# DecoderCircuit_M1.net
KiCad netlist of a schematic drawn in Altium Designer
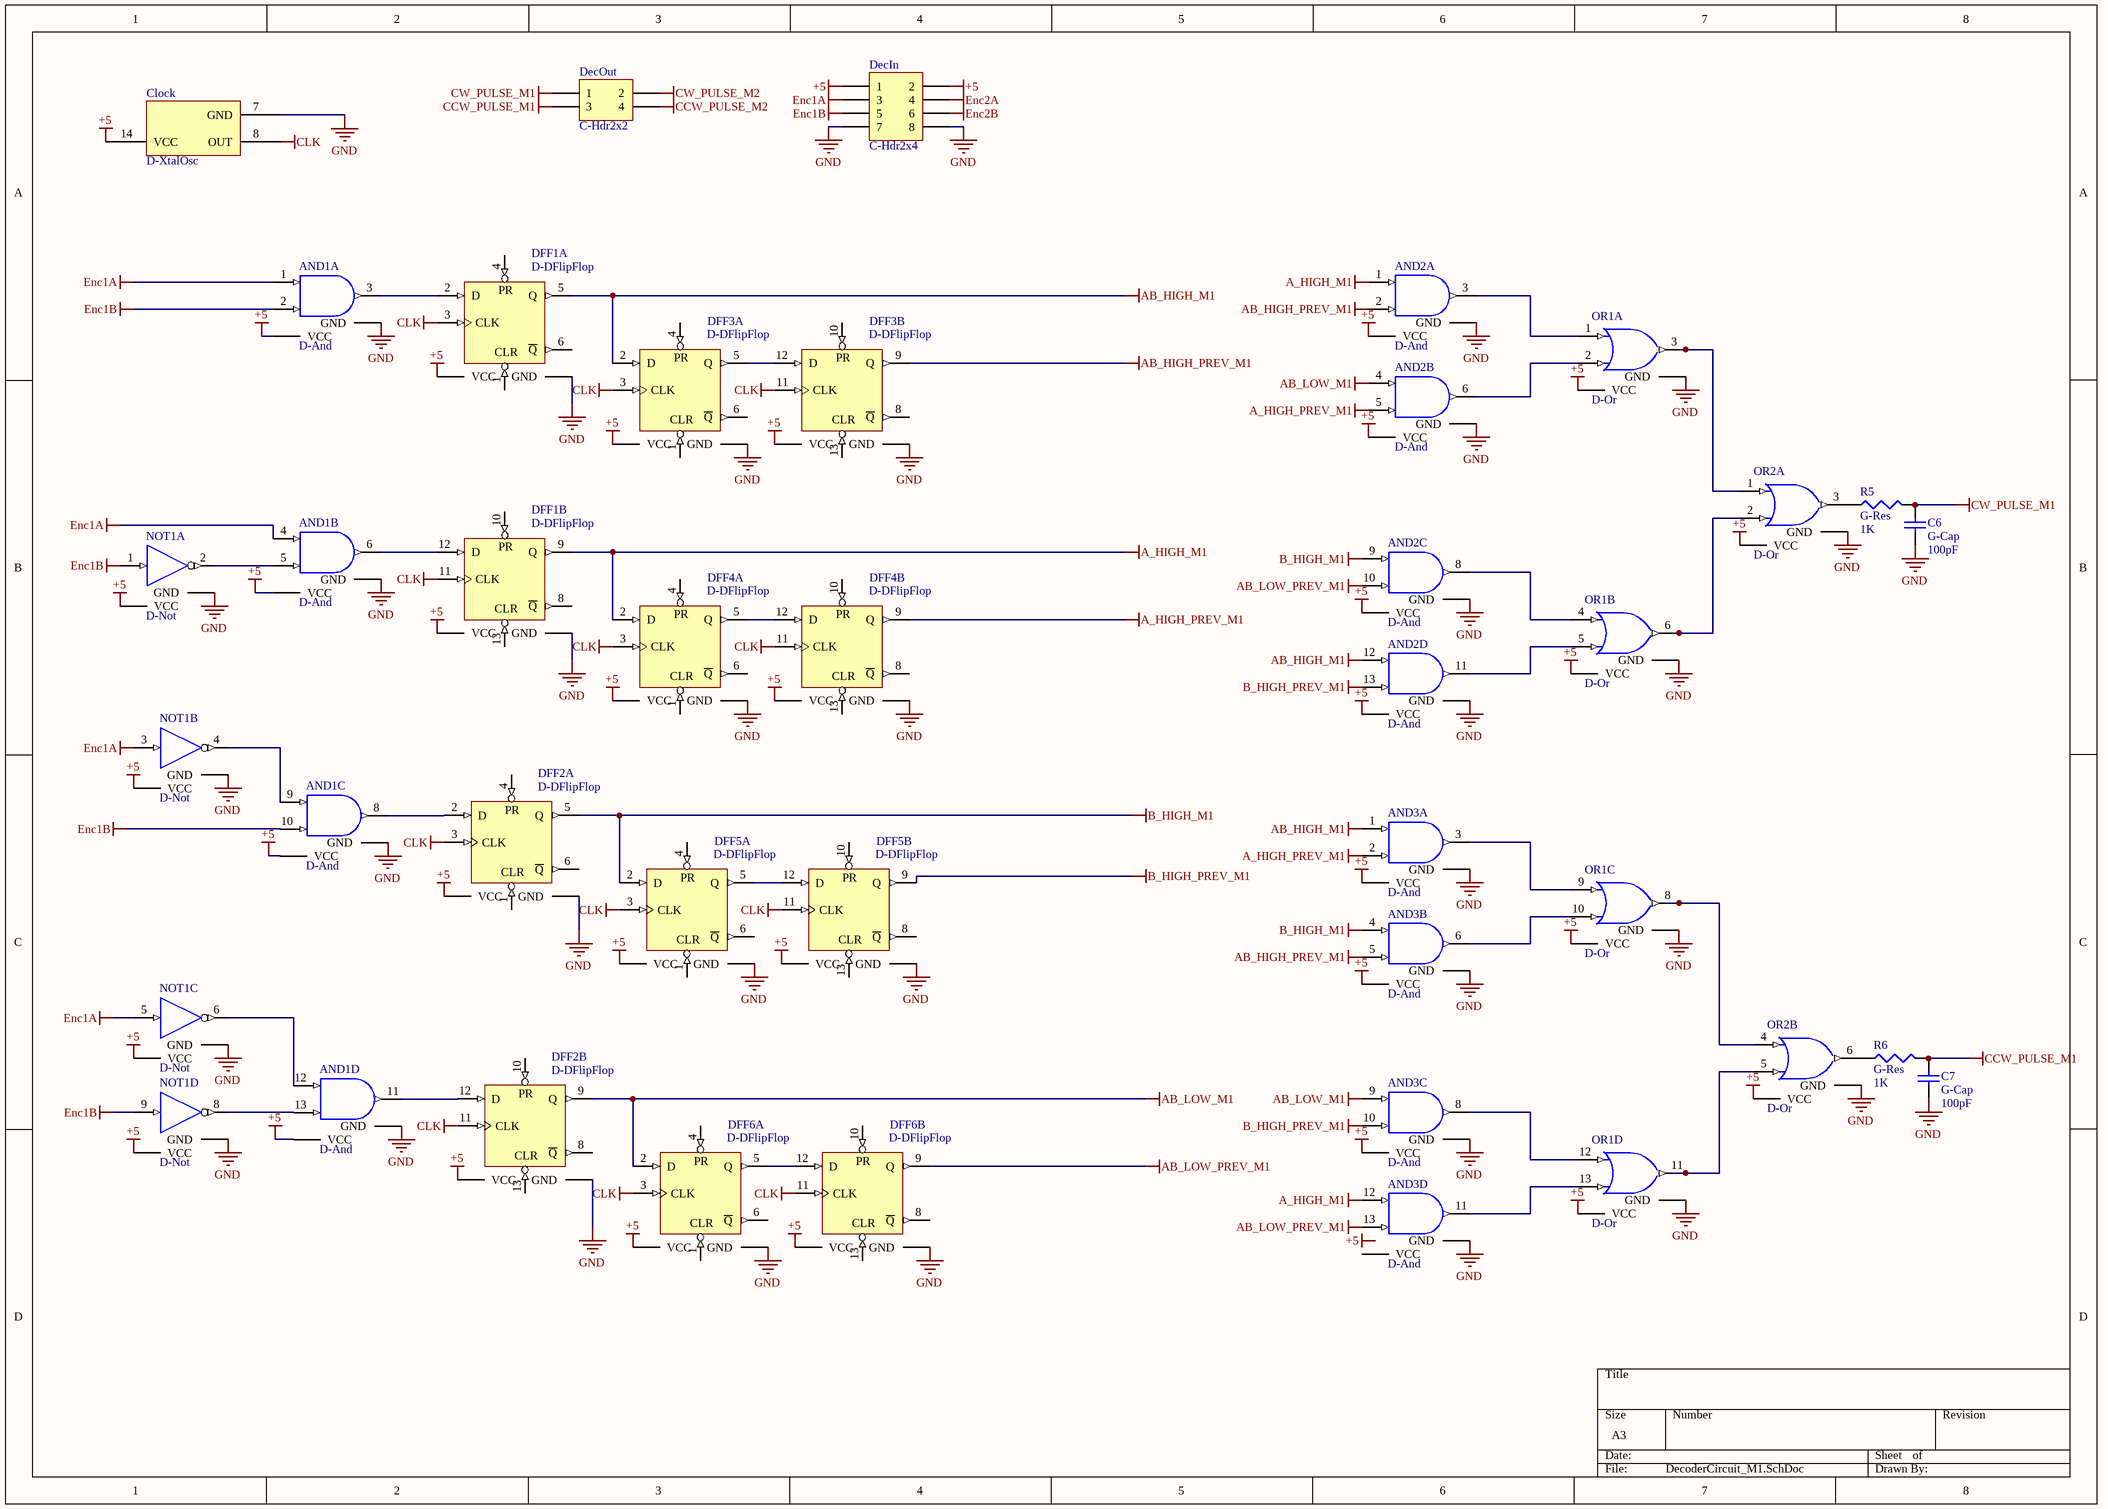
[diagram p0: DecoderCircuit_M1.SchDoc]

(export (version "E")
  (design (tool "Eeschema 10.0.6"))
  (components
    (comp (ref "AND1")
      (value "D-And")
      (footprint "DIP14_LGE1.0")
      (description "Quad 2-input AND gate")
      (fields (field (name "PUBLISHER") "Altium Limited"))
      (libsource (lib "PartsDatabaseV16.1") (part "D-And"))
    )
    (comp (ref "AND2")
      (value "D-And")
      (footprint "DIP14_LGE1.0")
      (description "Quad 2-input AND gate")
      (fields (field (name "PUBLISHER") "Altium Limited"))
      (libsource (lib "PartsDatabaseV16.1") (part "D-And"))
    )
    (comp (ref "AND3")
      (value "D-And")
      (footprint "DIP14_LGE1.0")
      (description "Quad 2-input AND gate")
      (fields (field (name "PUBLISHER") "Altium Limited"))
      (libsource (lib "PartsDatabaseV16.1") (part "D-And"))
    )
    (comp (ref "C6")
      (value "G-Cap")
      (footprint "Cap2.54mm_LGE1.0")
      (description "Capacitor (specify value)")
      (fields (field (name "ALTIUM_VALUE") "100pF") (field (name "PUBLISHER") "Altium Limited"))
      (libsource (lib "PartsDatabaseV16.1") (part "G-Cap"))
    )
    (comp (ref "C7")
      (value "G-Cap")
      (footprint "Cap2.54mm_LGE1.0")
      (description "Capacitor (specify value)")
      (fields (field (name "ALTIUM_VALUE") "100pF") (field (name "PUBLISHER") "Altium Limited"))
      (libsource (lib "PartsDatabaseV16.1") (part "G-Cap"))
    )
    (comp (ref "Clock")
      (value "D-XtalOsc")
      (footprint "4Lead Osc_LGE1.0")
      (description "Crystal Oscillator")
      (fields (field (name "PUBLISHER") "Altium Limited"))
      (libsource (lib "PartsDatabaseV16.1") (part "D-XtalOsc"))
    )
    (comp (ref "DecIn")
      (value "C-Hdr2x4")
      (footprint "HDR2X4_LGE1.0")
      (description "Header, 4-Pin, Dual row")
      (fields (field (name "PUBLISHER") "Altium Limited"))
      (libsource (lib "PartsDatabaseV16.1") (part "C-Hdr2x4"))
    )
    (comp (ref "DecOut")
      (value "C-Hdr2x2")
      (footprint "HDR2X2_LGE1.0")
      (description "Header, 2-Pin, Dual row")
      (fields (field (name "PUBLISHER") "Altium Limited"))
      (libsource (lib "PartsDatabaseV16.1") (part "C-Hdr2x2"))
    )
    (comp (ref "DFF1")
      (value "D-DFlipFlop")
      (footprint "DIP14_LGE1.0")
      (description "Dual D flip-flop")
      (fields (field (name "PUBLISHER") "Altium Limited"))
      (libsource (lib "PartsDatabaseV16.1") (part "D-DFlipFlop"))
    )
    (comp (ref "DFF2")
      (value "D-DFlipFlop")
      (footprint "DIP14_LGE1.0")
      (description "Dual D flip-flop")
      (fields (field (name "PUBLISHER") "Altium Limited"))
      (libsource (lib "PartsDatabaseV16.1") (part "D-DFlipFlop"))
    )
    (comp (ref "DFF3")
      (value "D-DFlipFlop")
      (footprint "DIP14_LGE1.0")
      (description "Dual D flip-flop")
      (fields (field (name "PUBLISHER") "Altium Limited"))
      (libsource (lib "PartsDatabaseV16.1") (part "D-DFlipFlop"))
    )
    (comp (ref "DFF4")
      (value "D-DFlipFlop")
      (footprint "DIP14_LGE1.0")
      (description "Dual D flip-flop")
      (fields (field (name "PUBLISHER") "Altium Limited"))
      (libsource (lib "PartsDatabaseV16.1") (part "D-DFlipFlop"))
    )
    (comp (ref "DFF5")
      (value "D-DFlipFlop")
      (footprint "DIP14_LGE1.0")
      (description "Dual D flip-flop")
      (fields (field (name "PUBLISHER") "Altium Limited"))
      (libsource (lib "PartsDatabaseV16.1") (part "D-DFlipFlop"))
    )
    (comp (ref "DFF6")
      (value "D-DFlipFlop")
      (footprint "DIP14_LGE1.0")
      (description "Dual D flip-flop")
      (fields (field (name "PUBLISHER") "Altium Limited"))
      (libsource (lib "PartsDatabaseV16.1") (part "D-DFlipFlop"))
    )
    (comp (ref "NOT1")
      (value "D-Not")
      (footprint "DIP14_LGE1.0")
      (description "Hex NOT gate (inverter)")
      (fields (field (name "PUBLISHER") "Altium Limited"))
      (libsource (lib "PartsDatabaseV16.1") (part "D-Not"))
    )
    (comp (ref "OR1")
      (value "D-Or")
      (footprint "DIP14_LGE1.0")
      (description "Quad 2-input OR gate")
      (fields (field (name "PUBLISHER") "Altium Limited"))
      (libsource (lib "PartsDatabaseV16.1") (part "D-Or"))
    )
    (comp (ref "OR2")
      (value "D-Or")
      (footprint "DIP14_LGE1.0")
      (description "Quad 2-input OR gate")
      (fields (field (name "PUBLISHER") "Altium Limited"))
      (libsource (lib "PartsDatabaseV16.1") (part "D-Or"))
    )
    (comp (ref "R5")
      (value "G-Res")
      (footprint "Res10mm_LGE1.0")
      (description "Resistor (specify value)")
      (fields (field (name "ALTIUM_VALUE") "1K") (field (name "PUBLISHER") "Altium Limited"))
      (libsource (lib "PartsDatabaseV16.1") (part "G-Res"))
    )
    (comp (ref "R6")
      (value "G-Res")
      (footprint "Res10mm_LGE1.0")
      (description "Resistor (specify value)")
      (fields (field (name "ALTIUM_VALUE") "1K") (field (name "PUBLISHER") "Altium Limited"))
      (libsource (lib "PartsDatabaseV16.1") (part "G-Res"))
    )
  )
  (nets
    (net (code "1") (name "+5") (class "Default")
      (node (ref "AND1") (pin "14") (pinfunction "VCC_14") (pintype "power_in"))
      (node (ref "AND2") (pin "14") (pinfunction "VCC_14") (pintype "power_in"))
      (node (ref "AND3") (pin "14") (pinfunction "VCC_14") (pintype "power_in"))
      (node (ref "Clock") (pin "14") (pinfunction "VCC_14") (pintype "passive"))
      (node (ref "DFF1") (pin "14") (pinfunction "VCC_14") (pintype "power_in"))
      (node (ref "DFF2") (pin "14") (pinfunction "VCC_14") (pintype "power_in"))
      (node (ref "DFF3") (pin "14") (pinfunction "VCC_14") (pintype "power_in"))
      (node (ref "DFF4") (pin "14") (pinfunction "VCC_14") (pintype "power_in"))
      (node (ref "DFF5") (pin "14") (pinfunction "VCC_14") (pintype "power_in"))
      (node (ref "DFF6") (pin "14") (pinfunction "VCC_14") (pintype "power_in"))
      (node (ref "DecIn") (pin "1") (pinfunction "1_1") (pintype "passive"))
      (node (ref "DecIn") (pin "2") (pinfunction "2_2") (pintype "passive"))
      (node (ref "NOT1") (pin "14") (pinfunction "VCC_14") (pintype "power_in"))
      (node (ref "OR1") (pin "14") (pinfunction "VCC_14") (pintype "power_in"))
      (node (ref "OR2") (pin "14") (pinfunction "VCC_14") (pintype "power_in"))
    )
    (net (code "2") (name "AB_HIGH_M1") (class "Default")
      (node (ref "AND2") (pin "12") (pinfunction "A_12") (pintype "input"))
      (node (ref "AND3") (pin "1") (pinfunction "A_1") (pintype "input"))
      (node (ref "DFF1") (pin "5") (pinfunction "Q_5") (pintype "output"))
      (node (ref "DFF3") (pin "2") (pinfunction "D_2") (pintype "input"))
    )
    (net (code "3") (name "AB_HIGH_PREV_M1") (class "Default")
      (node (ref "AND2") (pin "2") (pinfunction "B_2") (pintype "input"))
      (node (ref "AND3") (pin "5") (pinfunction "B_5") (pintype "input"))
      (node (ref "DFF3") (pin "9") (pinfunction "Q_9") (pintype "output"))
    )
    (net (code "4") (name "AB_LOW_M1") (class "Default")
      (node (ref "AND2") (pin "4") (pinfunction "A_4") (pintype "input"))
      (node (ref "AND3") (pin "9") (pinfunction "A_9") (pintype "input"))
      (node (ref "DFF2") (pin "9") (pinfunction "Q_9") (pintype "output"))
      (node (ref "DFF6") (pin "2") (pinfunction "D_2") (pintype "input"))
    )
    (net (code "5") (name "AB_LOW_PREV_M1") (class "Default")
      (node (ref "AND2") (pin "10") (pinfunction "B_10") (pintype "input"))
      (node (ref "AND3") (pin "13") (pinfunction "B_13") (pintype "input"))
      (node (ref "DFF6") (pin "9") (pinfunction "Q_9") (pintype "output"))
    )
    (net (code "6") (name "A_HIGH_M1") (class "Default")
      (node (ref "AND2") (pin "1") (pinfunction "A_1") (pintype "input"))
      (node (ref "AND3") (pin "12") (pinfunction "A_12") (pintype "input"))
      (node (ref "DFF1") (pin "9") (pinfunction "Q_9") (pintype "output"))
      (node (ref "DFF4") (pin "2") (pinfunction "D_2") (pintype "input"))
    )
    (net (code "7") (name "A_HIGH_PREV_M1") (class "Default")
      (node (ref "AND2") (pin "5") (pinfunction "B_5") (pintype "input"))
      (node (ref "AND3") (pin "2") (pinfunction "B_2") (pintype "input"))
      (node (ref "DFF4") (pin "9") (pinfunction "Q_9") (pintype "output"))
    )
    (net (code "8") (name "B_HIGH_M1") (class "Default")
      (node (ref "AND2") (pin "9") (pinfunction "A_9") (pintype "input"))
      (node (ref "AND3") (pin "4") (pinfunction "A_4") (pintype "input"))
      (node (ref "DFF2") (pin "5") (pinfunction "Q_5") (pintype "output"))
      (node (ref "DFF5") (pin "2") (pinfunction "D_2") (pintype "input"))
    )
    (net (code "9") (name "B_HIGH_PREV_M1") (class "Default")
      (node (ref "AND2") (pin "13") (pinfunction "B_13") (pintype "input"))
      (node (ref "AND3") (pin "10") (pinfunction "B_10") (pintype "input"))
      (node (ref "DFF5") (pin "9") (pinfunction "Q_9") (pintype "output"))
    )
    (net (code "10") (name "CCW_PULSE_M1") (class "Default")
      (node (ref "C7") (pin "1") (pinfunction "1_1") (pintype "passive"))
      (node (ref "DecOut") (pin "3") (pinfunction "3_3") (pintype "passive"))
      (node (ref "R6") (pin "2") (pinfunction "2_2") (pintype "passive"))
    )
    (net (code "11") (name "CCW_PULSE_M2") (class "Default")
      (node (ref "DecOut") (pin "4") (pinfunction "4_4") (pintype "passive"))
    )
    (net (code "12") (name "CLK") (class "Default")
      (node (ref "Clock") (pin "8") (pinfunction "OUT_8") (pintype "passive"))
      (node (ref "DFF1") (pin "11") (pinfunction "CLK_11") (pintype "input"))
      (node (ref "DFF1") (pin "3") (pinfunction "CLK_3") (pintype "input"))
      (node (ref "DFF2") (pin "11") (pinfunction "CLK_11") (pintype "input"))
      (node (ref "DFF2") (pin "3") (pinfunction "CLK_3") (pintype "input"))
      (node (ref "DFF3") (pin "11") (pinfunction "CLK_11") (pintype "input"))
      (node (ref "DFF3") (pin "3") (pinfunction "CLK_3") (pintype "input"))
      (node (ref "DFF4") (pin "11") (pinfunction "CLK_11") (pintype "input"))
      (node (ref "DFF4") (pin "3") (pinfunction "CLK_3") (pintype "input"))
      (node (ref "DFF5") (pin "11") (pinfunction "CLK_11") (pintype "input"))
      (node (ref "DFF5") (pin "3") (pinfunction "CLK_3") (pintype "input"))
      (node (ref "DFF6") (pin "11") (pinfunction "CLK_11") (pintype "input"))
      (node (ref "DFF6") (pin "3") (pinfunction "CLK_3") (pintype "input"))
    )
    (net (code "13") (name "CW_PULSE_M1") (class "Default")
      (node (ref "C6") (pin "1") (pinfunction "1_1") (pintype "passive"))
      (node (ref "DecOut") (pin "1") (pinfunction "1_1") (pintype "passive"))
      (node (ref "R5") (pin "2") (pinfunction "2_2") (pintype "passive"))
    )
    (net (code "14") (name "CW_PULSE_M2") (class "Default")
      (node (ref "DecOut") (pin "2") (pinfunction "2_2") (pintype "passive"))
    )
    (net (code "15") (name "Enc1A") (class "Default")
      (node (ref "AND1") (pin "1") (pinfunction "A_1") (pintype "input"))
      (node (ref "AND1") (pin "4") (pinfunction "A_4") (pintype "input"))
      (node (ref "DecIn") (pin "3") (pinfunction "3_3") (pintype "passive"))
      (node (ref "NOT1") (pin "3") (pinfunction "A_3") (pintype "input"))
      (node (ref "NOT1") (pin "5") (pinfunction "A_5") (pintype "input"))
    )
    (net (code "16") (name "Enc1B") (class "Default")
      (node (ref "AND1") (pin "10") (pinfunction "B_10") (pintype "input"))
      (node (ref "AND1") (pin "2") (pinfunction "B_2") (pintype "input"))
      (node (ref "DecIn") (pin "5") (pinfunction "5_5") (pintype "passive"))
      (node (ref "NOT1") (pin "1") (pinfunction "A_1") (pintype "input"))
      (node (ref "NOT1") (pin "9") (pinfunction "A_9") (pintype "input"))
    )
    (net (code "17") (name "Enc2A") (class "Default")
      (node (ref "DecIn") (pin "4") (pinfunction "4_4") (pintype "passive"))
    )
    (net (code "18") (name "Enc2B") (class "Default")
      (node (ref "DecIn") (pin "6") (pinfunction "6_6") (pintype "passive"))
    )
    (net (code "19") (name "GND") (class "Default")
      (node (ref "AND1") (pin "7") (pinfunction "GND_7") (pintype "power_in"))
      (node (ref "AND2") (pin "7") (pinfunction "GND_7") (pintype "power_in"))
      (node (ref "AND3") (pin "7") (pinfunction "GND_7") (pintype "power_in"))
      (node (ref "C6") (pin "2") (pinfunction "2_2") (pintype "passive"))
      (node (ref "C7") (pin "2") (pinfunction "2_2") (pintype "passive"))
      (node (ref "Clock") (pin "7") (pinfunction "GND_7") (pintype "passive"))
      (node (ref "DFF1") (pin "7") (pinfunction "GND_7") (pintype "power_in"))
      (node (ref "DFF2") (pin "7") (pinfunction "GND_7") (pintype "power_in"))
      (node (ref "DFF3") (pin "7") (pinfunction "GND_7") (pintype "power_in"))
      (node (ref "DFF4") (pin "7") (pinfunction "GND_7") (pintype "power_in"))
      (node (ref "DFF5") (pin "7") (pinfunction "GND_7") (pintype "power_in"))
      (node (ref "DFF6") (pin "7") (pinfunction "GND_7") (pintype "power_in"))
      (node (ref "DecIn") (pin "7") (pinfunction "7_7") (pintype "passive"))
      (node (ref "DecIn") (pin "8") (pinfunction "8_8") (pintype "passive"))
      (node (ref "NOT1") (pin "7") (pinfunction "GND_7") (pintype "power_in"))
      (node (ref "OR1") (pin "7") (pinfunction "GND_7") (pintype "power_in"))
      (node (ref "OR2") (pin "7") (pinfunction "GND_7") (pintype "power_in"))
    )
    (net (code "20") (name "Net-(AND1A-Y)") (class "Default")
      (node (ref "AND1") (pin "3") (pinfunction "Y_3") (pintype "output"))
      (node (ref "DFF1") (pin "2") (pinfunction "D_2") (pintype "input"))
    )
    (net (code "21") (name "Net-(AND1B-B)") (class "Default")
      (node (ref "AND1") (pin "5") (pinfunction "B_5") (pintype "input"))
      (node (ref "NOT1") (pin "2") (pinfunction "Y_2") (pintype "output"))
    )
    (net (code "22") (name "Net-(AND1B-Y)") (class "Default")
      (node (ref "AND1") (pin "6") (pinfunction "Y_6") (pintype "output"))
      (node (ref "DFF1") (pin "12") (pinfunction "D_12") (pintype "input"))
    )
    (net (code "23") (name "Net-(AND1C-A)") (class "Default")
      (node (ref "AND1") (pin "9") (pinfunction "A_9") (pintype "input"))
      (node (ref "NOT1") (pin "4") (pinfunction "Y_4") (pintype "output"))
    )
    (net (code "24") (name "Net-(AND1C-Y)") (class "Default")
      (node (ref "AND1") (pin "8") (pinfunction "Y_8") (pintype "output"))
      (node (ref "DFF2") (pin "2") (pinfunction "D_2") (pintype "input"))
    )
    (net (code "25") (name "Net-(AND1D-A)") (class "Default")
      (node (ref "AND1") (pin "12") (pinfunction "A_12") (pintype "input"))
      (node (ref "NOT1") (pin "6") (pinfunction "Y_6") (pintype "output"))
    )
    (net (code "26") (name "Net-(AND1D-B)") (class "Default")
      (node (ref "AND1") (pin "13") (pinfunction "B_13") (pintype "input"))
      (node (ref "NOT1") (pin "8") (pinfunction "Y_8") (pintype "output"))
    )
    (net (code "27") (name "Net-(AND1D-Y)") (class "Default")
      (node (ref "AND1") (pin "11") (pinfunction "Y_11") (pintype "output"))
      (node (ref "DFF2") (pin "12") (pinfunction "D_12") (pintype "input"))
    )
    (net (code "28") (name "Net-(AND2A-Y)") (class "Default")
      (node (ref "AND2") (pin "3") (pinfunction "Y_3") (pintype "output"))
      (node (ref "OR1") (pin "1") (pinfunction "A_1") (pintype "input"))
    )
    (net (code "29") (name "Net-(AND2B-Y)") (class "Default")
      (node (ref "AND2") (pin "6") (pinfunction "Y_6") (pintype "output"))
      (node (ref "OR1") (pin "2") (pinfunction "B_2") (pintype "input"))
    )
    (net (code "30") (name "Net-(AND2C-Y)") (class "Default")
      (node (ref "AND2") (pin "8") (pinfunction "Y_8") (pintype "output"))
      (node (ref "OR1") (pin "4") (pinfunction "A_4") (pintype "input"))
    )
    (net (code "31") (name "Net-(AND2D-Y)") (class "Default")
      (node (ref "AND2") (pin "11") (pinfunction "Y_11") (pintype "output"))
      (node (ref "OR1") (pin "5") (pinfunction "B_5") (pintype "input"))
    )
    (net (code "32") (name "Net-(AND3A-Y)") (class "Default")
      (node (ref "AND3") (pin "3") (pinfunction "Y_3") (pintype "output"))
      (node (ref "OR1") (pin "9") (pinfunction "A_9") (pintype "input"))
    )
    (net (code "33") (name "Net-(AND3B-Y)") (class "Default")
      (node (ref "AND3") (pin "6") (pinfunction "Y_6") (pintype "output"))
      (node (ref "OR1") (pin "10") (pinfunction "B_10") (pintype "input"))
    )
    (net (code "34") (name "Net-(AND3C-Y)") (class "Default")
      (node (ref "AND3") (pin "8") (pinfunction "Y_8") (pintype "output"))
      (node (ref "OR1") (pin "12") (pinfunction "A_12") (pintype "input"))
    )
    (net (code "35") (name "Net-(AND3D-Y)") (class "Default")
      (node (ref "AND3") (pin "11") (pinfunction "Y_11") (pintype "output"))
      (node (ref "OR1") (pin "13") (pinfunction "B_13") (pintype "input"))
    )
    (net (code "36") (name "Net-(DFF3A-Q)") (class "Default")
      (node (ref "DFF3") (pin "12") (pinfunction "D_12") (pintype "input"))
      (node (ref "DFF3") (pin "5") (pinfunction "Q_5") (pintype "output"))
    )
    (net (code "37") (name "Net-(DFF4A-Q)") (class "Default")
      (node (ref "DFF4") (pin "12") (pinfunction "D_12") (pintype "input"))
      (node (ref "DFF4") (pin "5") (pinfunction "Q_5") (pintype "output"))
    )
    (net (code "38") (name "Net-(DFF5A-Q)") (class "Default")
      (node (ref "DFF5") (pin "12") (pinfunction "D_12") (pintype "input"))
      (node (ref "DFF5") (pin "5") (pinfunction "Q_5") (pintype "output"))
    )
    (net (code "39") (name "Net-(DFF6A-Q)") (class "Default")
      (node (ref "DFF6") (pin "12") (pinfunction "D_12") (pintype "input"))
      (node (ref "DFF6") (pin "5") (pinfunction "Q_5") (pintype "output"))
    )
    (net (code "40") (name "Net-(OR1A-Y)") (class "Default")
      (node (ref "OR1") (pin "3") (pinfunction "Y_3") (pintype "output"))
      (node (ref "OR2") (pin "1") (pinfunction "A_1") (pintype "input"))
    )
    (net (code "41") (name "Net-(OR1B-Y)") (class "Default")
      (node (ref "OR1") (pin "6") (pinfunction "Y_6") (pintype "output"))
      (node (ref "OR2") (pin "2") (pinfunction "B_2") (pintype "input"))
    )
    (net (code "42") (name "Net-(OR1C-Y)") (class "Default")
      (node (ref "OR1") (pin "8") (pinfunction "Y_8") (pintype "output"))
      (node (ref "OR2") (pin "4") (pinfunction "A_4") (pintype "input"))
    )
    (net (code "43") (name "Net-(OR1D-Y)") (class "Default")
      (node (ref "OR1") (pin "11") (pinfunction "Y_11") (pintype "output"))
      (node (ref "OR2") (pin "5") (pinfunction "B_5") (pintype "input"))
    )
    (net (code "44") (name "Net-(OR2A-Y)") (class "Default")
      (node (ref "OR2") (pin "3") (pinfunction "Y_3") (pintype "output"))
      (node (ref "R5") (pin "1") (pinfunction "1_1") (pintype "passive"))
    )
    (net (code "45") (name "Net-(OR2B-Y)") (class "Default")
      (node (ref "OR2") (pin "6") (pinfunction "Y_6") (pintype "output"))
      (node (ref "R6") (pin "1") (pinfunction "1_1") (pintype "passive"))
    )
    (net (code "46") (name "unconnected-(AND3D-VCC-Pad14)") (class "Default")
      (node (ref "AND3") (pin "14") (pinfunction "VCC_14") (pintype "power_in"))
    )
    (net (code "47") (name "unconnected-(Clock-NC-Pad1)") (class "Default")
      (node (ref "Clock") (pin "1") (pinfunction "NC_1") (pintype "passive"))
    )
    (net (code "48") (name "unconnected-(DFF1A-CLR-Pad1)") (class "Default")
      (node (ref "DFF1") (pin "1") (pinfunction "CLR_1") (pintype "input"))
    )
    (net (code "49") (name "unconnected-(DFF1A-PR-Pad4)") (class "Default")
      (node (ref "DFF1") (pin "4") (pinfunction "PR_4") (pintype "input"))
    )
    (net (code "50") (name "unconnected-(DFF1A-~{Q}-Pad6)") (class "Default")
      (node (ref "DFF1") (pin "6") (pinfunction "~{Q}_6") (pintype "output"))
    )
    (net (code "51") (name "unconnected-(DFF1B-CLR-Pad13)") (class "Default")
      (node (ref "DFF1") (pin "13") (pinfunction "CLR_13") (pintype "input"))
    )
    (net (code "52") (name "unconnected-(DFF1B-PR-Pad10)") (class "Default")
      (node (ref "DFF1") (pin "10") (pinfunction "PR_10") (pintype "input"))
    )
    (net (code "53") (name "unconnected-(DFF1B-~{Q}-Pad8)") (class "Default")
      (node (ref "DFF1") (pin "8") (pinfunction "~{Q}_8") (pintype "output"))
    )
    (net (code "54") (name "unconnected-(DFF2A-CLR-Pad1)") (class "Default")
      (node (ref "DFF2") (pin "1") (pinfunction "CLR_1") (pintype "input"))
    )
    (net (code "55") (name "unconnected-(DFF2A-PR-Pad4)") (class "Default")
      (node (ref "DFF2") (pin "4") (pinfunction "PR_4") (pintype "input"))
    )
    (net (code "56") (name "unconnected-(DFF2A-~{Q}-Pad6)") (class "Default")
      (node (ref "DFF2") (pin "6") (pinfunction "~{Q}_6") (pintype "output"))
    )
    (net (code "57") (name "unconnected-(DFF2B-CLR-Pad13)") (class "Default")
      (node (ref "DFF2") (pin "13") (pinfunction "CLR_13") (pintype "input"))
    )
    (net (code "58") (name "unconnected-(DFF2B-PR-Pad10)") (class "Default")
      (node (ref "DFF2") (pin "10") (pinfunction "PR_10") (pintype "input"))
    )
    (net (code "59") (name "unconnected-(DFF2B-~{Q}-Pad8)") (class "Default")
      (node (ref "DFF2") (pin "8") (pinfunction "~{Q}_8") (pintype "output"))
    )
    (net (code "60") (name "unconnected-(DFF3A-CLR-Pad1)") (class "Default")
      (node (ref "DFF3") (pin "1") (pinfunction "CLR_1") (pintype "input"))
    )
    (net (code "61") (name "unconnected-(DFF3A-PR-Pad4)") (class "Default")
      (node (ref "DFF3") (pin "4") (pinfunction "PR_4") (pintype "input"))
    )
    (net (code "62") (name "unconnected-(DFF3A-~{Q}-Pad6)") (class "Default")
      (node (ref "DFF3") (pin "6") (pinfunction "~{Q}_6") (pintype "output"))
    )
    (net (code "63") (name "unconnected-(DFF3B-CLR-Pad13)") (class "Default")
      (node (ref "DFF3") (pin "13") (pinfunction "CLR_13") (pintype "input"))
    )
    (net (code "64") (name "unconnected-(DFF3B-PR-Pad10)") (class "Default")
      (node (ref "DFF3") (pin "10") (pinfunction "PR_10") (pintype "input"))
    )
    (net (code "65") (name "unconnected-(DFF3B-~{Q}-Pad8)") (class "Default")
      (node (ref "DFF3") (pin "8") (pinfunction "~{Q}_8") (pintype "output"))
    )
    (net (code "66") (name "unconnected-(DFF4A-CLR-Pad1)") (class "Default")
      (node (ref "DFF4") (pin "1") (pinfunction "CLR_1") (pintype "input"))
    )
    (net (code "67") (name "unconnected-(DFF4A-PR-Pad4)") (class "Default")
      (node (ref "DFF4") (pin "4") (pinfunction "PR_4") (pintype "input"))
    )
    (net (code "68") (name "unconnected-(DFF4A-~{Q}-Pad6)") (class "Default")
      (node (ref "DFF4") (pin "6") (pinfunction "~{Q}_6") (pintype "output"))
    )
    (net (code "69") (name "unconnected-(DFF4B-CLR-Pad13)") (class "Default")
      (node (ref "DFF4") (pin "13") (pinfunction "CLR_13") (pintype "input"))
    )
    (net (code "70") (name "unconnected-(DFF4B-PR-Pad10)") (class "Default")
      (node (ref "DFF4") (pin "10") (pinfunction "PR_10") (pintype "input"))
    )
    (net (code "71") (name "unconnected-(DFF4B-~{Q}-Pad8)") (class "Default")
      (node (ref "DFF4") (pin "8") (pinfunction "~{Q}_8") (pintype "output"))
    )
    (net (code "72") (name "unconnected-(DFF5A-CLR-Pad1)") (class "Default")
      (node (ref "DFF5") (pin "1") (pinfunction "CLR_1") (pintype "input"))
    )
    (net (code "73") (name "unconnected-(DFF5A-PR-Pad4)") (class "Default")
      (node (ref "DFF5") (pin "4") (pinfunction "PR_4") (pintype "input"))
    )
    (net (code "74") (name "unconnected-(DFF5A-~{Q}-Pad6)") (class "Default")
      (node (ref "DFF5") (pin "6") (pinfunction "~{Q}_6") (pintype "output"))
    )
    (net (code "75") (name "unconnected-(DFF5B-CLR-Pad13)") (class "Default")
      (node (ref "DFF5") (pin "13") (pinfunction "CLR_13") (pintype "input"))
    )
    (net (code "76") (name "unconnected-(DFF5B-PR-Pad10)") (class "Default")
      (node (ref "DFF5") (pin "10") (pinfunction "PR_10") (pintype "input"))
    )
    (net (code "77") (name "unconnected-(DFF5B-~{Q}-Pad8)") (class "Default")
      (node (ref "DFF5") (pin "8") (pinfunction "~{Q}_8") (pintype "output"))
    )
    (net (code "78") (name "unconnected-(DFF6A-CLR-Pad1)") (class "Default")
      (node (ref "DFF6") (pin "1") (pinfunction "CLR_1") (pintype "input"))
    )
    (net (code "79") (name "unconnected-(DFF6A-PR-Pad4)") (class "Default")
      (node (ref "DFF6") (pin "4") (pinfunction "PR_4") (pintype "input"))
    )
    (net (code "80") (name "unconnected-(DFF6A-~{Q}-Pad6)") (class "Default")
      (node (ref "DFF6") (pin "6") (pinfunction "~{Q}_6") (pintype "output"))
    )
    (net (code "81") (name "unconnected-(DFF6B-CLR-Pad13)") (class "Default")
      (node (ref "DFF6") (pin "13") (pinfunction "CLR_13") (pintype "input"))
    )
    (net (code "82") (name "unconnected-(DFF6B-PR-Pad10)") (class "Default")
      (node (ref "DFF6") (pin "10") (pinfunction "PR_10") (pintype "input"))
    )
    (net (code "83") (name "unconnected-(DFF6B-~{Q}-Pad8)") (class "Default")
      (node (ref "DFF6") (pin "8") (pinfunction "~{Q}_8") (pintype "output"))
    )
  )
)
